# SCH_MagControl_Sheet1.net
KiCad netlist of a schematic drawn in Altium Designer
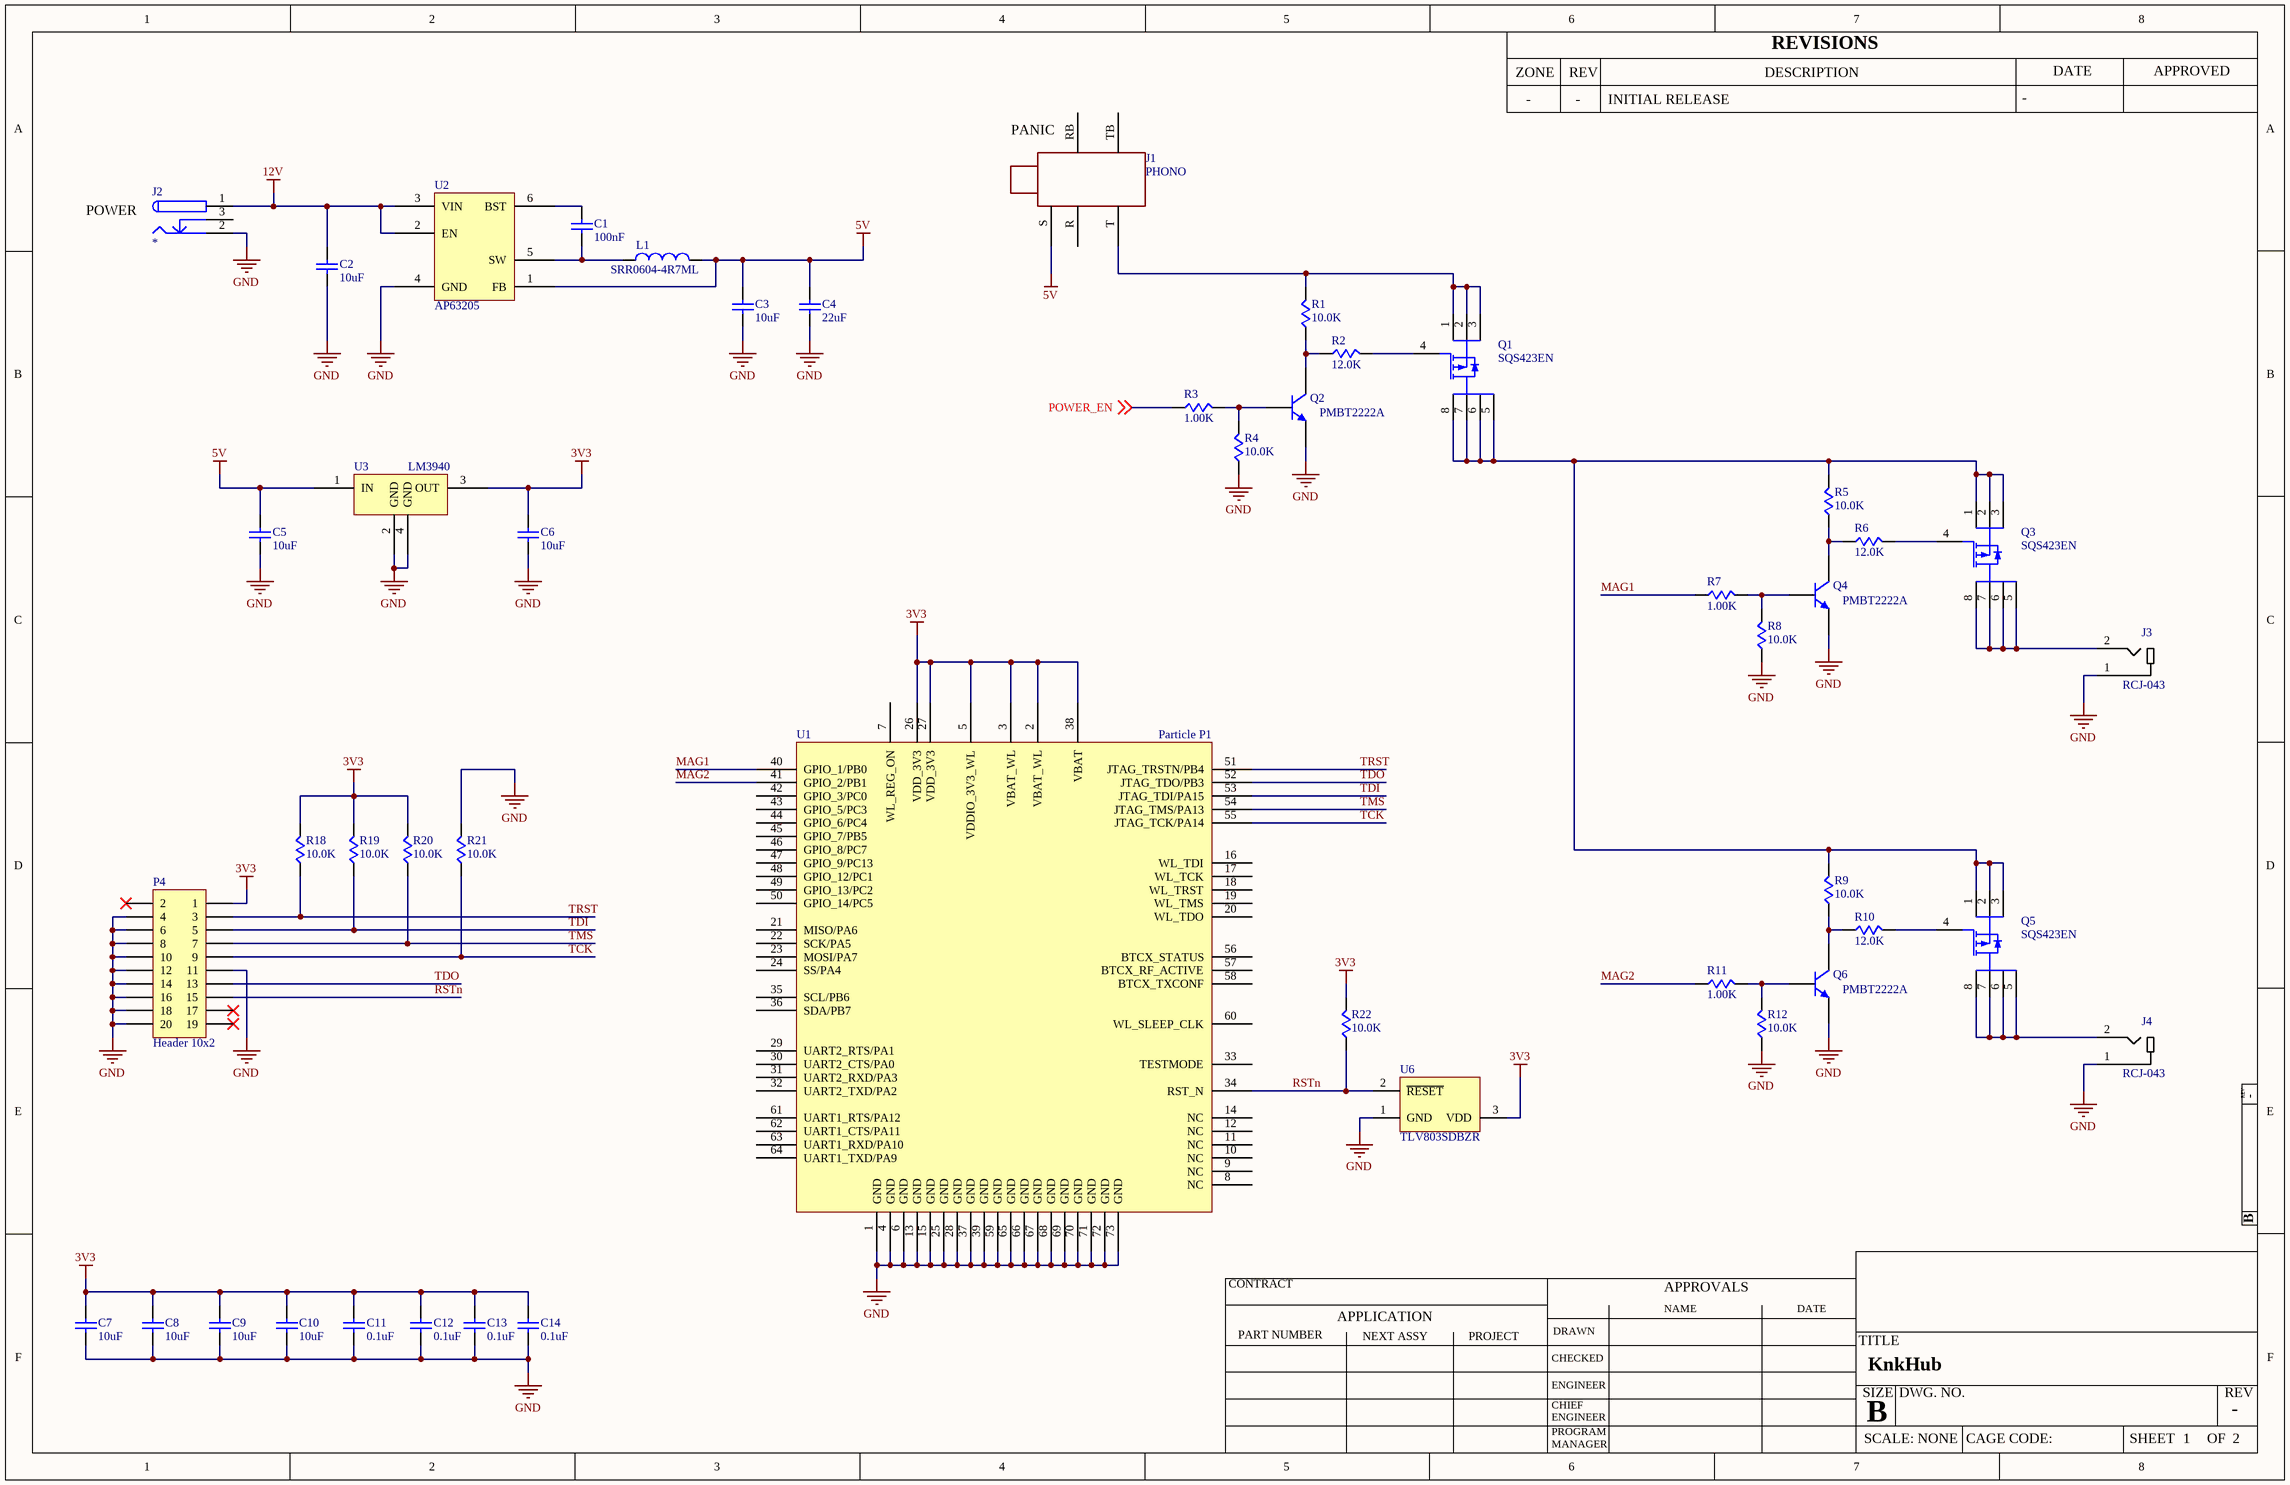
[diagram p0: SCH_MagControl_Sheet1.SchDoc]

(export (version "E")
  (design (tool "Eeschema 10.0.6"))
  (components
    (comp (ref "C1")
      (value "100nF")
      (footprint "CAPC1608L")
      (description "Capacitor (SMD)")
      (fields (field (name "TOLERANCE") "10%") (field (name "VOLTAGE") "16V"))
      (libsource (lib "MAST_Library") (part "Cap Semi"))
    )
    (comp (ref "C2")
      (value "10uF")
      (footprint "CAPC2012L")
      (description "Capacitor (SMD)")
      (fields (field (name "TOLERANCE") "10%") (field (name "VOLTAGE") "16V"))
      (libsource (lib "MAST_Library") (part "Cap Semi"))
    )
    (comp (ref "C3")
      (value "10uF")
      (footprint "CAPC2012L")
      (description "Capacitor (SMD)")
      (fields (field (name "TOLERANCE") "10%") (field (name "VOLTAGE") "16V"))
      (libsource (lib "MAST_Library") (part "Cap Semi"))
    )
    (comp (ref "C4")
      (value "22uF")
      (footprint "CAPC2012L")
      (description "Capacitor (SMD)")
      (fields (field (name "TOLERANCE") "10%"))
      (libsource (lib "MAST_Library") (part "Cap Semi"))
    )
    (comp (ref "C5")
      (value "10uF")
      (footprint "CAPC1608L")
      (description "Capacitor (SMD)")
      (fields (field (name "TOLERANCE") "20%") (field (name "VOLTAGE") "6.3V"))
      (libsource (lib "MAST_Library") (part "Cap Semi"))
    )
    (comp (ref "C6")
      (value "10uF")
      (footprint "CAPC1608L")
      (description "Capacitor (SMD)")
      (fields (field (name "TOLERANCE") "20%") (field (name "VOLTAGE") "6.3V"))
      (libsource (lib "MAST_Library") (part "Cap Semi"))
    )
    (comp (ref "C7")
      (value "10uF")
      (footprint "CAPC1608L")
      (description "Capacitor (SMD)")
      (fields (field (name "TOLERANCE") "20%") (field (name "VOLTAGE") "6.3V"))
      (libsource (lib "MAST_Library") (part "Cap Semi"))
    )
    (comp (ref "C8")
      (value "10uF")
      (footprint "CAPC1608L")
      (description "Capacitor (SMD)")
      (fields (field (name "TOLERANCE") "20%") (field (name "VOLTAGE") "6.3V"))
      (libsource (lib "MAST_Library") (part "Cap Semi"))
    )
    (comp (ref "C9")
      (value "10uF")
      (footprint "CAPC1608L")
      (description "Capacitor (SMD)")
      (fields (field (name "TOLERANCE") "20%") (field (name "VOLTAGE") "6.3V"))
      (libsource (lib "MAST_Library") (part "Cap Semi"))
    )
    (comp (ref "C10")
      (value "10uF")
      (footprint "CAPC1608L")
      (description "Capacitor (SMD)")
      (fields (field (name "TOLERANCE") "20%") (field (name "VOLTAGE") "6.3V"))
      (libsource (lib "MAST_Library") (part "Cap Semi"))
    )
    (comp (ref "C11")
      (value "0.1uF")
      (footprint "CAPC2012L")
      (description "Capacitor (SMD)")
      (fields (field (name "TOLERANCE") "20%"))
      (libsource (lib "MAST_Library") (part "Cap Semi"))
    )
    (comp (ref "C12")
      (value "0.1uF")
      (footprint "CAPC2012L")
      (description "Capacitor (SMD)")
      (fields (field (name "TOLERANCE") "20%"))
      (libsource (lib "MAST_Library") (part "Cap Semi"))
    )
    (comp (ref "C13")
      (value "0.1uF")
      (footprint "CAPC2012L")
      (description "Capacitor (SMD)")
      (fields (field (name "TOLERANCE") "20%"))
      (libsource (lib "MAST_Library") (part "Cap Semi"))
    )
    (comp (ref "C14")
      (value "0.1uF")
      (footprint "CAPC2012L")
      (description "Capacitor (SMD)")
      (fields (field (name "TOLERANCE") "20%"))
      (libsource (lib "MAST_Library") (part "Cap Semi"))
    )
    (comp (ref "J1") (value "PHONO") (footprint "SN37A12") (libsource (lib "HCG_Library") (part "PHONO_250")))
    (comp (ref "J2")
      (value "~")
      (footprint "PJ-002B-SMT")
      (description "Low Voltage Power Supply Connector")
      (fields (field (name "ALTIUM_VALUE") "*"))
      (libsource (lib "HCG_Library") (part "PWR2.5"))
    )
    (comp (ref "J3")
      (value "RCJ-043")
      (footprint "CUI_RCJ-043")
      (description "CONN RCA JACK MONO 3.2MM R/A")
      (libsource (lib "HCG_Library") (part "RCJ-043"))
    )
    (comp (ref "J4")
      (value "RCJ-043")
      (footprint "CUI_RCJ-043")
      (description "CONN RCA JACK MONO 3.2MM R/A")
      (libsource (lib "HCG_Library") (part "RCJ-043"))
    )
    (comp (ref "L1")
      (value "SRR0604-4R7ML")
      (footprint "IND_BOURNS_SRR06")
      (description "Inductor")
      (fields (field (name "TOLERANCE") "20%"))
      (libsource (lib "HCG_Library") (part "Inductor"))
    )
    (comp (ref "P4")
      (value "Header 10x2")
      (footprint "C-5103308-5")
      (libsource (lib "HCG_Library") (part "HEADER10X2"))
    )
    (comp (ref "Q1")
      (value "SQS423EN")
      (footprint "POWER-PAK 1212-8")
      (description "MOSFET P-CH PPAK-8")
      (libsource (lib "Schlib_MAST") (part "MOSFET-P_PPAK"))
    )
    (comp (ref "Q2")
      (value "PMBT2222A")
      (footprint "SOT23_N")
      (description "TRANS NPN SW 600MA 40V SOT23")
      (libsource (lib "Philips Discrete BJT - Low Power") (part "PMBT2222"))
    )
    (comp (ref "Q3")
      (value "SQS423EN")
      (footprint "POWER-PAK 1212-8")
      (description "MOSFET P-CH PPAK-8")
      (libsource (lib "Schlib_MAST") (part "MOSFET-P_PPAK"))
    )
    (comp (ref "Q4")
      (value "PMBT2222A")
      (footprint "SOT23_N")
      (description "TRANS NPN SW 600MA 40V SOT23")
      (libsource (lib "Philips Discrete BJT - Low Power") (part "PMBT2222"))
    )
    (comp (ref "Q5")
      (value "SQS423EN")
      (footprint "POWER-PAK 1212-8")
      (description "MOSFET P-CH PPAK-8")
      (libsource (lib "Schlib_MAST") (part "MOSFET-P_PPAK"))
    )
    (comp (ref "Q6")
      (value "PMBT2222A")
      (footprint "SOT23_N")
      (description "TRANS NPN SW 600MA 40V SOT23")
      (libsource (lib "Philips Discrete BJT - Low Power") (part "PMBT2222"))
    )
    (comp (ref "R1")
      (value "10.0K")
      (footprint "RESC1005N")
      (description "RES 10.0K OHM 1/10W 1% 0402 SMD")
      (fields (field (name "TOLERANCE") "1%"))
      (libsource (lib "MAST_Library") (part "R"))
    )
    (comp (ref "R2")
      (value "12.0K")
      (footprint "RESC1005N")
      (description "RES 12.0K OHM 1/10W 1% 0402 SMD")
      (fields (field (name "TOLERANCE") "1%"))
      (libsource (lib "MAST_Library") (part "R"))
    )
    (comp (ref "R3")
      (value "1.00K")
      (footprint "RESC1005N")
      (description "RES 1.00K OHM 1/10W 1% 0402 SMD")
      (fields (field (name "TOLERANCE") "1%"))
      (libsource (lib "MAST_Library") (part "R"))
    )
    (comp (ref "R4")
      (value "10.0K")
      (footprint "RESC1005N")
      (description "RES 10.0K OHM 1/10W 1% 0402 SMD")
      (fields (field (name "TOLERANCE") "1%"))
      (libsource (lib "MAST_Library") (part "R"))
    )
    (comp (ref "R5")
      (value "10.0K")
      (footprint "RESC1005N")
      (description "RES 10.0K OHM 1/10W 1% 0402 SMD")
      (fields (field (name "TOLERANCE") "1%"))
      (libsource (lib "MAST_Library") (part "R"))
    )
    (comp (ref "R6")
      (value "12.0K")
      (footprint "RESC1005N")
      (description "RES 12.0K OHM 1/10W 1% 0402 SMD")
      (fields (field (name "TOLERANCE") "1%"))
      (libsource (lib "MAST_Library") (part "R"))
    )
    (comp (ref "R7")
      (value "1.00K")
      (footprint "RESC1005N")
      (description "RES 1.00K OHM 1/10W 1% 0402 SMD")
      (fields (field (name "TOLERANCE") "1%"))
      (libsource (lib "MAST_Library") (part "R"))
    )
    (comp (ref "R8")
      (value "10.0K")
      (footprint "RESC1005N")
      (description "RES 10.0K OHM 1/10W 1% 0402 SMD")
      (fields (field (name "TOLERANCE") "1%"))
      (libsource (lib "MAST_Library") (part "R"))
    )
    (comp (ref "R9")
      (value "10.0K")
      (footprint "RESC1005N")
      (description "RES 10.0K OHM 1/10W 1% 0402 SMD")
      (fields (field (name "TOLERANCE") "1%"))
      (libsource (lib "MAST_Library") (part "R"))
    )
    (comp (ref "R10")
      (value "12.0K")
      (footprint "RESC1005N")
      (description "RES 12.0K OHM 1/10W 1% 0402 SMD")
      (fields (field (name "TOLERANCE") "1%"))
      (libsource (lib "MAST_Library") (part "R"))
    )
    (comp (ref "R11")
      (value "1.00K")
      (footprint "RESC1005N")
      (description "RES 1.00K OHM 1/10W 1% 0402 SMD")
      (fields (field (name "TOLERANCE") "1%"))
      (libsource (lib "MAST_Library") (part "R"))
    )
    (comp (ref "R12")
      (value "10.0K")
      (footprint "RESC1005N")
      (description "RES 10.0K OHM 1/10W 1% 0402 SMD")
      (fields (field (name "TOLERANCE") "1%"))
      (libsource (lib "MAST_Library") (part "R"))
    )
    (comp (ref "R18")
      (value "10.0K")
      (footprint "RESC1005N")
      (description "RES 1.00K OHM 1/10W 1% 0402 SMD")
      (fields (field (name "TOLERANCE") "1%"))
      (libsource (lib "MAST_Library") (part "R"))
    )
    (comp (ref "R19")
      (value "10.0K")
      (footprint "RESC1005N")
      (description "RES 1.00K OHM 1/10W 1% 0402 SMD")
      (fields (field (name "TOLERANCE") "1%"))
      (libsource (lib "MAST_Library") (part "R"))
    )
    (comp (ref "R20")
      (value "10.0K")
      (footprint "RESC1005N")
      (description "RES 1.00K OHM 1/10W 1% 0402 SMD")
      (fields (field (name "TOLERANCE") "1%"))
      (libsource (lib "MAST_Library") (part "R"))
    )
    (comp (ref "R21")
      (value "10.0K")
      (footprint "RESC1005N")
      (description "RES 1.00K OHM 1/10W 1% 0402 SMD")
      (fields (field (name "TOLERANCE") "1%"))
      (libsource (lib "MAST_Library") (part "R"))
    )
    (comp (ref "R22")
      (value "10.0K")
      (footprint "RESC1005N")
      (description "RES 1.00K OHM 1/10W 1% 0402 SMD")
      (fields (field (name "TOLERANCE") "1%"))
      (libsource (lib "MAST_Library") (part "R"))
    )
    (comp (ref "U1")
      (value "Particle P1")
      (footprint "PARTICLE_P1")
      (description "P1 WI-FI MODULE")
      (libsource (lib "HCG_Library") (part "PARTICLE_P1"))
    )
    (comp (ref "U2")
      (value "AP63205")
      (footprint "TSOT26-6N")
      (description "IC REG BUCK 5V 2A TSOT26")
      (libsource (lib "HCG_Library") (part "AP63205"))
    )
    (comp (ref "U3")
      (value "LM3940")
      (footprint "SOT223-4N")
      (description "IC REG LDO 1A 5V SOT-223")
      (libsource (lib "HCG_Library") (part "LM3940"))
    )
    (comp (ref "U6")
      (value "TLV803SDBZR")
      (footprint "DBZ0003A_L")
      (description "IC VOLT SUPERVISR 2.93V SOT23-3")
      (fields (field (name "MANUFACTURER") "Texas Instruments"))
      (libsource (lib "HCG_Library") (part "TLV803SDBZR"))
    )
  )
  (nets
    (net (code "2") (name "/MAG1") (class "Default")
      (node (ref "R7") (pin "1") (pinfunction "1_1") (pintype "passive"))
      (node (ref "U1") (pin "40") (pinfunction "GPIO_1/PB0_40") (pintype "passive"))
    )
    (net (code "3") (name "/MAG2") (class "Default")
      (node (ref "R11") (pin "1") (pinfunction "1_1") (pintype "passive"))
      (node (ref "U1") (pin "41") (pinfunction "GPIO_2/PB1_41") (pintype "passive"))
    )
    (net (code "4") (name "/RSTn") (class "Default")
      (node (ref "P4") (pin "15") (pinfunction "15_15") (pintype "passive"))
      (node (ref "R22") (pin "1") (pinfunction "1_1") (pintype "passive"))
      (node (ref "U1") (pin "34") (pinfunction "RST_N_34") (pintype "passive"))
      (node (ref "U6") (pin "2") (pinfunction "~{RESET}_2") (pintype "open_collector"))
    )
    (net (code "5") (name "/TCK") (class "Default")
      (node (ref "P4") (pin "9") (pinfunction "9_9") (pintype "passive"))
      (node (ref "R21") (pin "1") (pinfunction "1_1") (pintype "passive"))
      (node (ref "U1") (pin "55") (pinfunction "JTAG_TCK/PA14_55") (pintype "passive"))
    )
    (net (code "6") (name "/TDI") (class "Default")
      (node (ref "P4") (pin "5") (pinfunction "5_5") (pintype "passive"))
      (node (ref "R19") (pin "1") (pinfunction "1_1") (pintype "passive"))
      (node (ref "U1") (pin "53") (pinfunction "JTAG_TDI/PA15_53") (pintype "passive"))
    )
    (net (code "7") (name "/TDO") (class "Default")
      (node (ref "P4") (pin "13") (pinfunction "13_13") (pintype "passive"))
      (node (ref "U1") (pin "52") (pinfunction "JTAG_TDO/PB3_52") (pintype "passive"))
    )
    (net (code "8") (name "/TMS") (class "Default")
      (node (ref "P4") (pin "7") (pinfunction "7_7") (pintype "passive"))
      (node (ref "R20") (pin "1") (pinfunction "1_1") (pintype "passive"))
      (node (ref "U1") (pin "54") (pinfunction "JTAG_TMS/PA13_54") (pintype "passive"))
    )
    (net (code "9") (name "/TRST") (class "Default")
      (node (ref "P4") (pin "3") (pinfunction "3_3") (pintype "passive"))
      (node (ref "R18") (pin "1") (pinfunction "1_1") (pintype "passive"))
      (node (ref "U1") (pin "51") (pinfunction "JTAG_TRSTN/PB4_51") (pintype "passive"))
    )
    (net (code "10") (name "3V3") (class "Default")
      (node (ref "C10") (pin "2") (pinfunction "2_2") (pintype "passive"))
      (node (ref "C11") (pin "2") (pinfunction "2_2") (pintype "passive"))
      (node (ref "C12") (pin "2") (pinfunction "2_2") (pintype "passive"))
      (node (ref "C13") (pin "2") (pinfunction "2_2") (pintype "passive"))
      (node (ref "C14") (pin "2") (pinfunction "2_2") (pintype "passive"))
      (node (ref "C6") (pin "2") (pinfunction "2_2") (pintype "passive"))
      (node (ref "C7") (pin "2") (pinfunction "2_2") (pintype "passive"))
      (node (ref "C8") (pin "2") (pinfunction "2_2") (pintype "passive"))
      (node (ref "C9") (pin "2") (pinfunction "2_2") (pintype "passive"))
      (node (ref "P4") (pin "1") (pinfunction "1_1") (pintype "passive"))
      (node (ref "R18") (pin "2") (pinfunction "2_2") (pintype "passive"))
      (node (ref "R19") (pin "2") (pinfunction "2_2") (pintype "passive"))
      (node (ref "R20") (pin "2") (pinfunction "2_2") (pintype "passive"))
      (node (ref "R22") (pin "2") (pinfunction "2_2") (pintype "passive"))
      (node (ref "U1") (pin "2") (pinfunction "VBAT_WL_2") (pintype "passive"))
      (node (ref "U1") (pin "26") (pinfunction "VDD_3V3_26") (pintype "passive"))
      (node (ref "U1") (pin "27") (pinfunction "VDD_3V3_27") (pintype "passive"))
      (node (ref "U1") (pin "3") (pinfunction "VBAT_WL_3") (pintype "passive"))
      (node (ref "U1") (pin "38") (pinfunction "VBAT_38") (pintype "passive"))
      (node (ref "U1") (pin "5") (pinfunction "VDDIO_3V3_WL_5") (pintype "passive"))
      (node (ref "U3") (pin "3") (pinfunction "OUT_3") (pintype "power_in"))
      (node (ref "U6") (pin "3") (pinfunction "VDD_3") (pintype "power_in"))
    )
    (net (code "11") (name "5V") (class "Default")
      (node (ref "C3") (pin "2") (pinfunction "2_2") (pintype "passive"))
      (node (ref "C4") (pin "2") (pinfunction "2_2") (pintype "passive"))
      (node (ref "C5") (pin "2") (pinfunction "2_2") (pintype "passive"))
      (node (ref "J1") (pin "S") (pinfunction "S_S") (pintype "passive"))
      (node (ref "L1") (pin "2") (pinfunction "2_2") (pintype "passive"))
      (node (ref "U2") (pin "1") (pinfunction "FB_1") (pintype "passive"))
      (node (ref "U3") (pin "1") (pinfunction "IN_1") (pintype "power_in"))
    )
    (net (code "12") (name "12V") (class "Default")
      (node (ref "C2") (pin "2") (pinfunction "2_2") (pintype "passive"))
      (node (ref "J2") (pin "1") (pinfunction "1_1") (pintype "passive"))
      (node (ref "U2") (pin "2") (pinfunction "EN_2") (pintype "passive"))
      (node (ref "U2") (pin "3") (pinfunction "VIN_3") (pintype "passive"))
    )
    (net (code "13") (name "GND") (class "Default")
      (node (ref "C10") (pin "1") (pinfunction "1_1") (pintype "passive"))
      (node (ref "C11") (pin "1") (pinfunction "1_1") (pintype "passive"))
      (node (ref "C12") (pin "1") (pinfunction "1_1") (pintype "passive"))
      (node (ref "C13") (pin "1") (pinfunction "1_1") (pintype "passive"))
      (node (ref "C14") (pin "1") (pinfunction "1_1") (pintype "passive"))
      (node (ref "C2") (pin "1") (pinfunction "1_1") (pintype "passive"))
      (node (ref "C3") (pin "1") (pinfunction "1_1") (pintype "passive"))
      (node (ref "C4") (pin "1") (pinfunction "1_1") (pintype "passive"))
      (node (ref "C5") (pin "1") (pinfunction "1_1") (pintype "passive"))
      (node (ref "C6") (pin "1") (pinfunction "1_1") (pintype "passive"))
      (node (ref "C7") (pin "1") (pinfunction "1_1") (pintype "passive"))
      (node (ref "C8") (pin "1") (pinfunction "1_1") (pintype "passive"))
      (node (ref "C9") (pin "1") (pinfunction "1_1") (pintype "passive"))
      (node (ref "J2") (pin "2") (pinfunction "2_2") (pintype "passive"))
      (node (ref "J3") (pin "1") (pinfunction "1_1") (pintype "passive"))
      (node (ref "J4") (pin "1") (pinfunction "1_1") (pintype "passive"))
      (node (ref "P4") (pin "10") (pinfunction "10_10") (pintype "passive"))
      (node (ref "P4") (pin "11") (pinfunction "11_11") (pintype "passive"))
      (node (ref "P4") (pin "12") (pinfunction "12_12") (pintype "passive"))
      (node (ref "P4") (pin "14") (pinfunction "14_14") (pintype "passive"))
      (node (ref "P4") (pin "16") (pinfunction "16_16") (pintype "passive"))
      (node (ref "P4") (pin "18") (pinfunction "18_18") (pintype "passive"))
      (node (ref "P4") (pin "20") (pinfunction "20_20") (pintype "passive"))
      (node (ref "P4") (pin "4") (pinfunction "4_4") (pintype "passive"))
      (node (ref "P4") (pin "6") (pinfunction "6_6") (pintype "passive"))
      (node (ref "P4") (pin "8") (pinfunction "8_8") (pintype "passive"))
      (node (ref "Q2") (pin "2") (pinfunction "E_2") (pintype "passive"))
      (node (ref "Q4") (pin "2") (pinfunction "E_2") (pintype "passive"))
      (node (ref "Q6") (pin "2") (pinfunction "E_2") (pintype "passive"))
      (node (ref "R12") (pin "1") (pinfunction "1_1") (pintype "passive"))
      (node (ref "R21") (pin "2") (pinfunction "2_2") (pintype "passive"))
      (node (ref "R4") (pin "1") (pinfunction "1_1") (pintype "passive"))
      (node (ref "R8") (pin "1") (pinfunction "1_1") (pintype "passive"))
      (node (ref "U1") (pin "1") (pinfunction "GND_1") (pintype "passive"))
      (node (ref "U1") (pin "13") (pinfunction "GND_13") (pintype "passive"))
      (node (ref "U1") (pin "15") (pinfunction "GND_15") (pintype "passive"))
      (node (ref "U1") (pin "25") (pinfunction "GND_25") (pintype "passive"))
      (node (ref "U1") (pin "28") (pinfunction "GND_28") (pintype "passive"))
      (node (ref "U1") (pin "37") (pinfunction "GND_37") (pintype "passive"))
      (node (ref "U1") (pin "39") (pinfunction "GND_39") (pintype "passive"))
      (node (ref "U1") (pin "4") (pinfunction "GND_4") (pintype "passive"))
      (node (ref "U1") (pin "59") (pinfunction "GND_59") (pintype "passive"))
      (node (ref "U1") (pin "6") (pinfunction "GND_6") (pintype "passive"))
      (node (ref "U1") (pin "65") (pinfunction "GND_65") (pintype "passive"))
      (node (ref "U1") (pin "66") (pinfunction "GND_66") (pintype "passive"))
      (node (ref "U1") (pin "67") (pinfunction "GND_67") (pintype "passive"))
      (node (ref "U1") (pin "68") (pinfunction "GND_68") (pintype "passive"))
      (node (ref "U1") (pin "69") (pinfunction "GND_69") (pintype "passive"))
      (node (ref "U1") (pin "70") (pinfunction "GND_70") (pintype "passive"))
      (node (ref "U1") (pin "71") (pinfunction "GND_71") (pintype "passive"))
      (node (ref "U1") (pin "72") (pinfunction "GND_72") (pintype "passive"))
      (node (ref "U1") (pin "73") (pinfunction "GND_73") (pintype "passive"))
      (node (ref "U2") (pin "4") (pinfunction "GND_4") (pintype "passive"))
      (node (ref "U3") (pin "2") (pinfunction "GND_2") (pintype "power_in"))
      (node (ref "U3") (pin "4") (pinfunction "GND_4") (pintype "passive"))
      (node (ref "U6") (pin "1") (pinfunction "GND_1") (pintype "power_in"))
    )
    (net (code "14") (name "Net-(J1-PadT)") (class "Default")
      (node (ref "J1") (pin "T") (pinfunction "T_T") (pintype "passive"))
      (node (ref "Q1") (pin "1") (pinfunction "S_1") (pintype "passive"))
      (node (ref "Q1") (pin "2") (pinfunction "S_2") (pintype "passive"))
      (node (ref "Q1") (pin "3") (pinfunction "S_3") (pintype "passive"))
      (node (ref "R1") (pin "2") (pinfunction "2_2") (pintype "passive"))
    )
    (net (code "15") (name "Net-(J3-Pad2)") (class "Default")
      (node (ref "J3") (pin "2") (pinfunction "2_2") (pintype "passive"))
      (node (ref "Q3") (pin "5") (pinfunction "D_5") (pintype "passive"))
      (node (ref "Q3") (pin "6") (pinfunction "D_6") (pintype "passive"))
      (node (ref "Q3") (pin "7") (pinfunction "D_7") (pintype "passive"))
      (node (ref "Q3") (pin "8") (pinfunction "D_8") (pintype "passive"))
    )
    (net (code "16") (name "Net-(J4-Pad2)") (class "Default")
      (node (ref "J4") (pin "2") (pinfunction "2_2") (pintype "passive"))
      (node (ref "Q5") (pin "5") (pinfunction "D_5") (pintype "passive"))
      (node (ref "Q5") (pin "6") (pinfunction "D_6") (pintype "passive"))
      (node (ref "Q5") (pin "7") (pinfunction "D_7") (pintype "passive"))
      (node (ref "Q5") (pin "8") (pinfunction "D_8") (pintype "passive"))
    )
    (net (code "17") (name "Net-(Q1-D-Pad5)") (class "Default")
      (node (ref "Q1") (pin "5") (pinfunction "D_5") (pintype "passive"))
      (node (ref "Q1") (pin "6") (pinfunction "D_6") (pintype "passive"))
      (node (ref "Q1") (pin "7") (pinfunction "D_7") (pintype "passive"))
      (node (ref "Q1") (pin "8") (pinfunction "D_8") (pintype "passive"))
      (node (ref "Q3") (pin "1") (pinfunction "S_1") (pintype "passive"))
      (node (ref "Q3") (pin "2") (pinfunction "S_2") (pintype "passive"))
      (node (ref "Q3") (pin "3") (pinfunction "S_3") (pintype "passive"))
      (node (ref "Q5") (pin "1") (pinfunction "S_1") (pintype "passive"))
      (node (ref "Q5") (pin "2") (pinfunction "S_2") (pintype "passive"))
      (node (ref "Q5") (pin "3") (pinfunction "S_3") (pintype "passive"))
      (node (ref "R5") (pin "2") (pinfunction "2_2") (pintype "passive"))
      (node (ref "R9") (pin "2") (pinfunction "2_2") (pintype "passive"))
    )
    (net (code "18") (name "Net-(Q1-G)") (class "Default")
      (node (ref "Q1") (pin "4") (pinfunction "G_4") (pintype "passive"))
      (node (ref "R2") (pin "2") (pinfunction "2_2") (pintype "passive"))
    )
    (net (code "19") (name "Net-(Q2-B)") (class "Default")
      (node (ref "Q2") (pin "1") (pinfunction "B_1") (pintype "passive"))
      (node (ref "R3") (pin "2") (pinfunction "2_2") (pintype "passive"))
      (node (ref "R4") (pin "2") (pinfunction "2_2") (pintype "passive"))
    )
    (net (code "20") (name "Net-(Q2-C)") (class "Default")
      (node (ref "Q2") (pin "3") (pinfunction "C_3") (pintype "passive"))
      (node (ref "R1") (pin "1") (pinfunction "1_1") (pintype "passive"))
      (node (ref "R2") (pin "1") (pinfunction "1_1") (pintype "passive"))
    )
    (net (code "21") (name "Net-(Q3-G)") (class "Default")
      (node (ref "Q3") (pin "4") (pinfunction "G_4") (pintype "passive"))
      (node (ref "R6") (pin "2") (pinfunction "2_2") (pintype "passive"))
    )
    (net (code "22") (name "Net-(Q4-B)") (class "Default")
      (node (ref "Q4") (pin "1") (pinfunction "B_1") (pintype "passive"))
      (node (ref "R7") (pin "2") (pinfunction "2_2") (pintype "passive"))
      (node (ref "R8") (pin "2") (pinfunction "2_2") (pintype "passive"))
    )
    (net (code "23") (name "Net-(Q4-C)") (class "Default")
      (node (ref "Q4") (pin "3") (pinfunction "C_3") (pintype "passive"))
      (node (ref "R5") (pin "1") (pinfunction "1_1") (pintype "passive"))
      (node (ref "R6") (pin "1") (pinfunction "1_1") (pintype "passive"))
    )
    (net (code "24") (name "Net-(Q5-G)") (class "Default")
      (node (ref "Q5") (pin "4") (pinfunction "G_4") (pintype "passive"))
      (node (ref "R10") (pin "2") (pinfunction "2_2") (pintype "passive"))
    )
    (net (code "25") (name "Net-(Q6-B)") (class "Default")
      (node (ref "Q6") (pin "1") (pinfunction "B_1") (pintype "passive"))
      (node (ref "R11") (pin "2") (pinfunction "2_2") (pintype "passive"))
      (node (ref "R12") (pin "2") (pinfunction "2_2") (pintype "passive"))
    )
    (net (code "26") (name "Net-(Q6-C)") (class "Default")
      (node (ref "Q6") (pin "3") (pinfunction "C_3") (pintype "passive"))
      (node (ref "R10") (pin "1") (pinfunction "1_1") (pintype "passive"))
      (node (ref "R9") (pin "1") (pinfunction "1_1") (pintype "passive"))
    )
    (net (code "27") (name "Net-(U2-BST)") (class "Default")
      (node (ref "C1") (pin "2") (pinfunction "2_2") (pintype "passive"))
      (node (ref "U2") (pin "6") (pinfunction "BST_6") (pintype "passive"))
    )
    (net (code "28") (name "Net-(U2-SW)") (class "Default")
      (node (ref "C1") (pin "1") (pinfunction "1_1") (pintype "passive"))
      (node (ref "L1") (pin "1") (pinfunction "1_1") (pintype "passive"))
      (node (ref "U2") (pin "5") (pinfunction "SW_5") (pintype "passive"))
    )
    (net (code "29") (name "POWER_EN") (class "Default")
      (node (ref "R3") (pin "1") (pinfunction "1_1") (pintype "passive"))
    )
    (net (code "30") (name "unconnected-(J1-PadR)") (class "Default")
      (node (ref "J1") (pin "R") (pinfunction "R_R") (pintype "passive"))
    )
    (net (code "31") (name "unconnected-(J1-PadRB)") (class "Default")
      (node (ref "J1") (pin "RB") (pinfunction "RB_RB") (pintype "passive"))
    )
    (net (code "32") (name "unconnected-(J1-PadTB)") (class "Default")
      (node (ref "J1") (pin "TB") (pinfunction "TB_TB") (pintype "passive"))
    )
    (net (code "33") (name "unconnected-(J2-Pad3)") (class "Default")
      (node (ref "J2") (pin "3") (pinfunction "3_3") (pintype "passive"))
    )
    (net (code "34") (name "unconnected-(P4-Pad2)") (class "Default")
      (node (ref "P4") (pin "2") (pinfunction "2_2") (pintype "passive+no_connect"))
    )
    (net (code "35") (name "unconnected-(P4-Pad17)") (class "Default")
      (node (ref "P4") (pin "17") (pinfunction "17_17") (pintype "passive+no_connect"))
    )
    (net (code "36") (name "unconnected-(P4-Pad19)") (class "Default")
      (node (ref "P4") (pin "19") (pinfunction "19_19") (pintype "passive+no_connect"))
    )
    (net (code "37") (name "unconnected-(U1-BTCX_RF_ACTIVE-Pad57)") (class "Default")
      (node (ref "U1") (pin "57") (pinfunction "BTCX_RF_ACTIVE_57") (pintype "passive"))
    )
    (net (code "38") (name "unconnected-(U1-BTCX_STATUS-Pad56)") (class "Default")
      (node (ref "U1") (pin "56") (pinfunction "BTCX_STATUS_56") (pintype "passive"))
    )
    (net (code "39") (name "unconnected-(U1-BTCX_TXCONF-Pad58)") (class "Default")
      (node (ref "U1") (pin "58") (pinfunction "BTCX_TXCONF_58") (pintype "passive"))
    )
    (net (code "40") (name "unconnected-(U1-GPIO_3{slash}PC0-Pad42)") (class "Default")
      (node (ref "U1") (pin "42") (pinfunction "GPIO_3/PC0_42") (pintype "passive"))
    )
    (net (code "41") (name "unconnected-(U1-GPIO_5{slash}PC3-Pad43)") (class "Default")
      (node (ref "U1") (pin "43") (pinfunction "GPIO_5/PC3_43") (pintype "passive"))
    )
    (net (code "42") (name "unconnected-(U1-GPIO_6{slash}PC4-Pad44)") (class "Default")
      (node (ref "U1") (pin "44") (pinfunction "GPIO_6/PC4_44") (pintype "passive"))
    )
    (net (code "43") (name "unconnected-(U1-GPIO_7{slash}PB5-Pad45)") (class "Default")
      (node (ref "U1") (pin "45") (pinfunction "GPIO_7/PB5_45") (pintype "passive"))
    )
    (net (code "44") (name "unconnected-(U1-GPIO_8{slash}PC7-Pad46)") (class "Default")
      (node (ref "U1") (pin "46") (pinfunction "GPIO_8/PC7_46") (pintype "passive"))
    )
    (net (code "45") (name "unconnected-(U1-GPIO_9{slash}PC13-Pad47)") (class "Default")
      (node (ref "U1") (pin "47") (pinfunction "GPIO_9/PC13_47") (pintype "passive"))
    )
    (net (code "46") (name "unconnected-(U1-GPIO_12{slash}PC1-Pad48)") (class "Default")
      (node (ref "U1") (pin "48") (pinfunction "GPIO_12/PC1_48") (pintype "passive"))
    )
    (net (code "47") (name "unconnected-(U1-GPIO_13{slash}PC2-Pad49)") (class "Default")
      (node (ref "U1") (pin "49") (pinfunction "GPIO_13/PC2_49") (pintype "passive"))
    )
    (net (code "48") (name "unconnected-(U1-GPIO_14{slash}PC5-Pad50)") (class "Default")
      (node (ref "U1") (pin "50") (pinfunction "GPIO_14/PC5_50") (pintype "passive"))
    )
    (net (code "49") (name "unconnected-(U1-MISO{slash}PA6-Pad21)") (class "Default")
      (node (ref "U1") (pin "21") (pinfunction "MISO/PA6_21") (pintype "passive"))
    )
    (net (code "50") (name "unconnected-(U1-MOSI{slash}PA7-Pad23)") (class "Default")
      (node (ref "U1") (pin "23") (pinfunction "MOSI/PA7_23") (pintype "passive"))
    )
    (net (code "51") (name "unconnected-(U1-NC-Pad8)") (class "Default")
      (node (ref "U1") (pin "8") (pinfunction "NC_8") (pintype "passive"))
    )
    (net (code "52") (name "unconnected-(U1-NC-Pad9)") (class "Default")
      (node (ref "U1") (pin "9") (pinfunction "NC_9") (pintype "passive"))
    )
    (net (code "53") (name "unconnected-(U1-NC-Pad10)") (class "Default")
      (node (ref "U1") (pin "10") (pinfunction "NC_10") (pintype "passive"))
    )
    (net (code "54") (name "unconnected-(U1-NC-Pad11)") (class "Default")
      (node (ref "U1") (pin "11") (pinfunction "NC_11") (pintype "passive"))
    )
    (net (code "55") (name "unconnected-(U1-NC-Pad12)") (class "Default")
      (node (ref "U1") (pin "12") (pinfunction "NC_12") (pintype "passive"))
    )
    (net (code "56") (name "unconnected-(U1-NC-Pad14)") (class "Default")
      (node (ref "U1") (pin "14") (pinfunction "NC_14") (pintype "passive"))
    )
    (net (code "57") (name "unconnected-(U1-SCK{slash}PA5-Pad22)") (class "Default")
      (node (ref "U1") (pin "22") (pinfunction "SCK/PA5_22") (pintype "passive"))
    )
    (net (code "58") (name "unconnected-(U1-SCL{slash}PB6-Pad35)") (class "Default")
      (node (ref "U1") (pin "35") (pinfunction "SCL/PB6_35") (pintype "passive"))
    )
    (net (code "59") (name "unconnected-(U1-SDA{slash}PB7-Pad36)") (class "Default")
      (node (ref "U1") (pin "36") (pinfunction "SDA/PB7_36") (pintype "passive"))
    )
    (net (code "60") (name "unconnected-(U1-SS{slash}PA4-Pad24)") (class "Default")
      (node (ref "U1") (pin "24") (pinfunction "SS/PA4_24") (pintype "passive"))
    )
    (net (code "61") (name "unconnected-(U1-TESTMODE-Pad33)") (class "Default")
      (node (ref "U1") (pin "33") (pinfunction "TESTMODE_33") (pintype "passive"))
    )
    (net (code "62") (name "unconnected-(U1-UART1_CTS{slash}PA11-Pad62)") (class "Default")
      (node (ref "U1") (pin "62") (pinfunction "UART1_CTS/PA11_62") (pintype "passive"))
    )
    (net (code "63") (name "unconnected-(U1-UART1_RTS{slash}PA12-Pad61)") (class "Default")
      (node (ref "U1") (pin "61") (pinfunction "UART1_RTS/PA12_61") (pintype "passive"))
    )
    (net (code "64") (name "unconnected-(U1-UART1_RXD{slash}PA10-Pad63)") (class "Default")
      (node (ref "U1") (pin "63") (pinfunction "UART1_RXD/PA10_63") (pintype "passive"))
    )
    (net (code "65") (name "unconnected-(U1-UART1_TXD{slash}PA9-Pad64)") (class "Default")
      (node (ref "U1") (pin "64") (pinfunction "UART1_TXD/PA9_64") (pintype "passive"))
    )
    (net (code "66") (name "unconnected-(U1-UART2_CTS{slash}PA0-Pad30)") (class "Default")
      (node (ref "U1") (pin "30") (pinfunction "UART2_CTS/PA0_30") (pintype "passive"))
    )
    (net (code "67") (name "unconnected-(U1-UART2_RTS{slash}PA1-Pad29)") (class "Default")
      (node (ref "U1") (pin "29") (pinfunction "UART2_RTS/PA1_29") (pintype "passive"))
    )
    (net (code "68") (name "unconnected-(U1-UART2_RXD{slash}PA3-Pad31)") (class "Default")
      (node (ref "U1") (pin "31") (pinfunction "UART2_RXD/PA3_31") (pintype "passive"))
    )
    (net (code "69") (name "unconnected-(U1-UART2_TXD{slash}PA2-Pad32)") (class "Default")
      (node (ref "U1") (pin "32") (pinfunction "UART2_TXD/PA2_32") (pintype "passive"))
    )
    (net (code "70") (name "unconnected-(U1-WL_REG_ON-Pad7)") (class "Default")
      (node (ref "U1") (pin "7") (pinfunction "WL_REG_ON_7") (pintype "passive"))
    )
    (net (code "71") (name "unconnected-(U1-WL_SLEEP_CLK-Pad60)") (class "Default")
      (node (ref "U1") (pin "60") (pinfunction "WL_SLEEP_CLK_60") (pintype "passive"))
    )
    (net (code "72") (name "unconnected-(U1-WL_TCK-Pad17)") (class "Default")
      (node (ref "U1") (pin "17") (pinfunction "WL_TCK_17") (pintype "passive"))
    )
    (net (code "73") (name "unconnected-(U1-WL_TDI-Pad16)") (class "Default")
      (node (ref "U1") (pin "16") (pinfunction "WL_TDI_16") (pintype "passive"))
    )
    (net (code "74") (name "unconnected-(U1-WL_TDO-Pad20)") (class "Default")
      (node (ref "U1") (pin "20") (pinfunction "WL_TDO_20") (pintype "passive"))
    )
    (net (code "75") (name "unconnected-(U1-WL_TMS-Pad19)") (class "Default")
      (node (ref "U1") (pin "19") (pinfunction "WL_TMS_19") (pintype "passive"))
    )
    (net (code "76") (name "unconnected-(U1-WL_TRST-Pad18)") (class "Default")
      (node (ref "U1") (pin "18") (pinfunction "WL_TRST_18") (pintype "passive"))
    )
  )
)
